# MB_pwr_in.net
KiCad netlist of a schematic drawn in Altium Designer
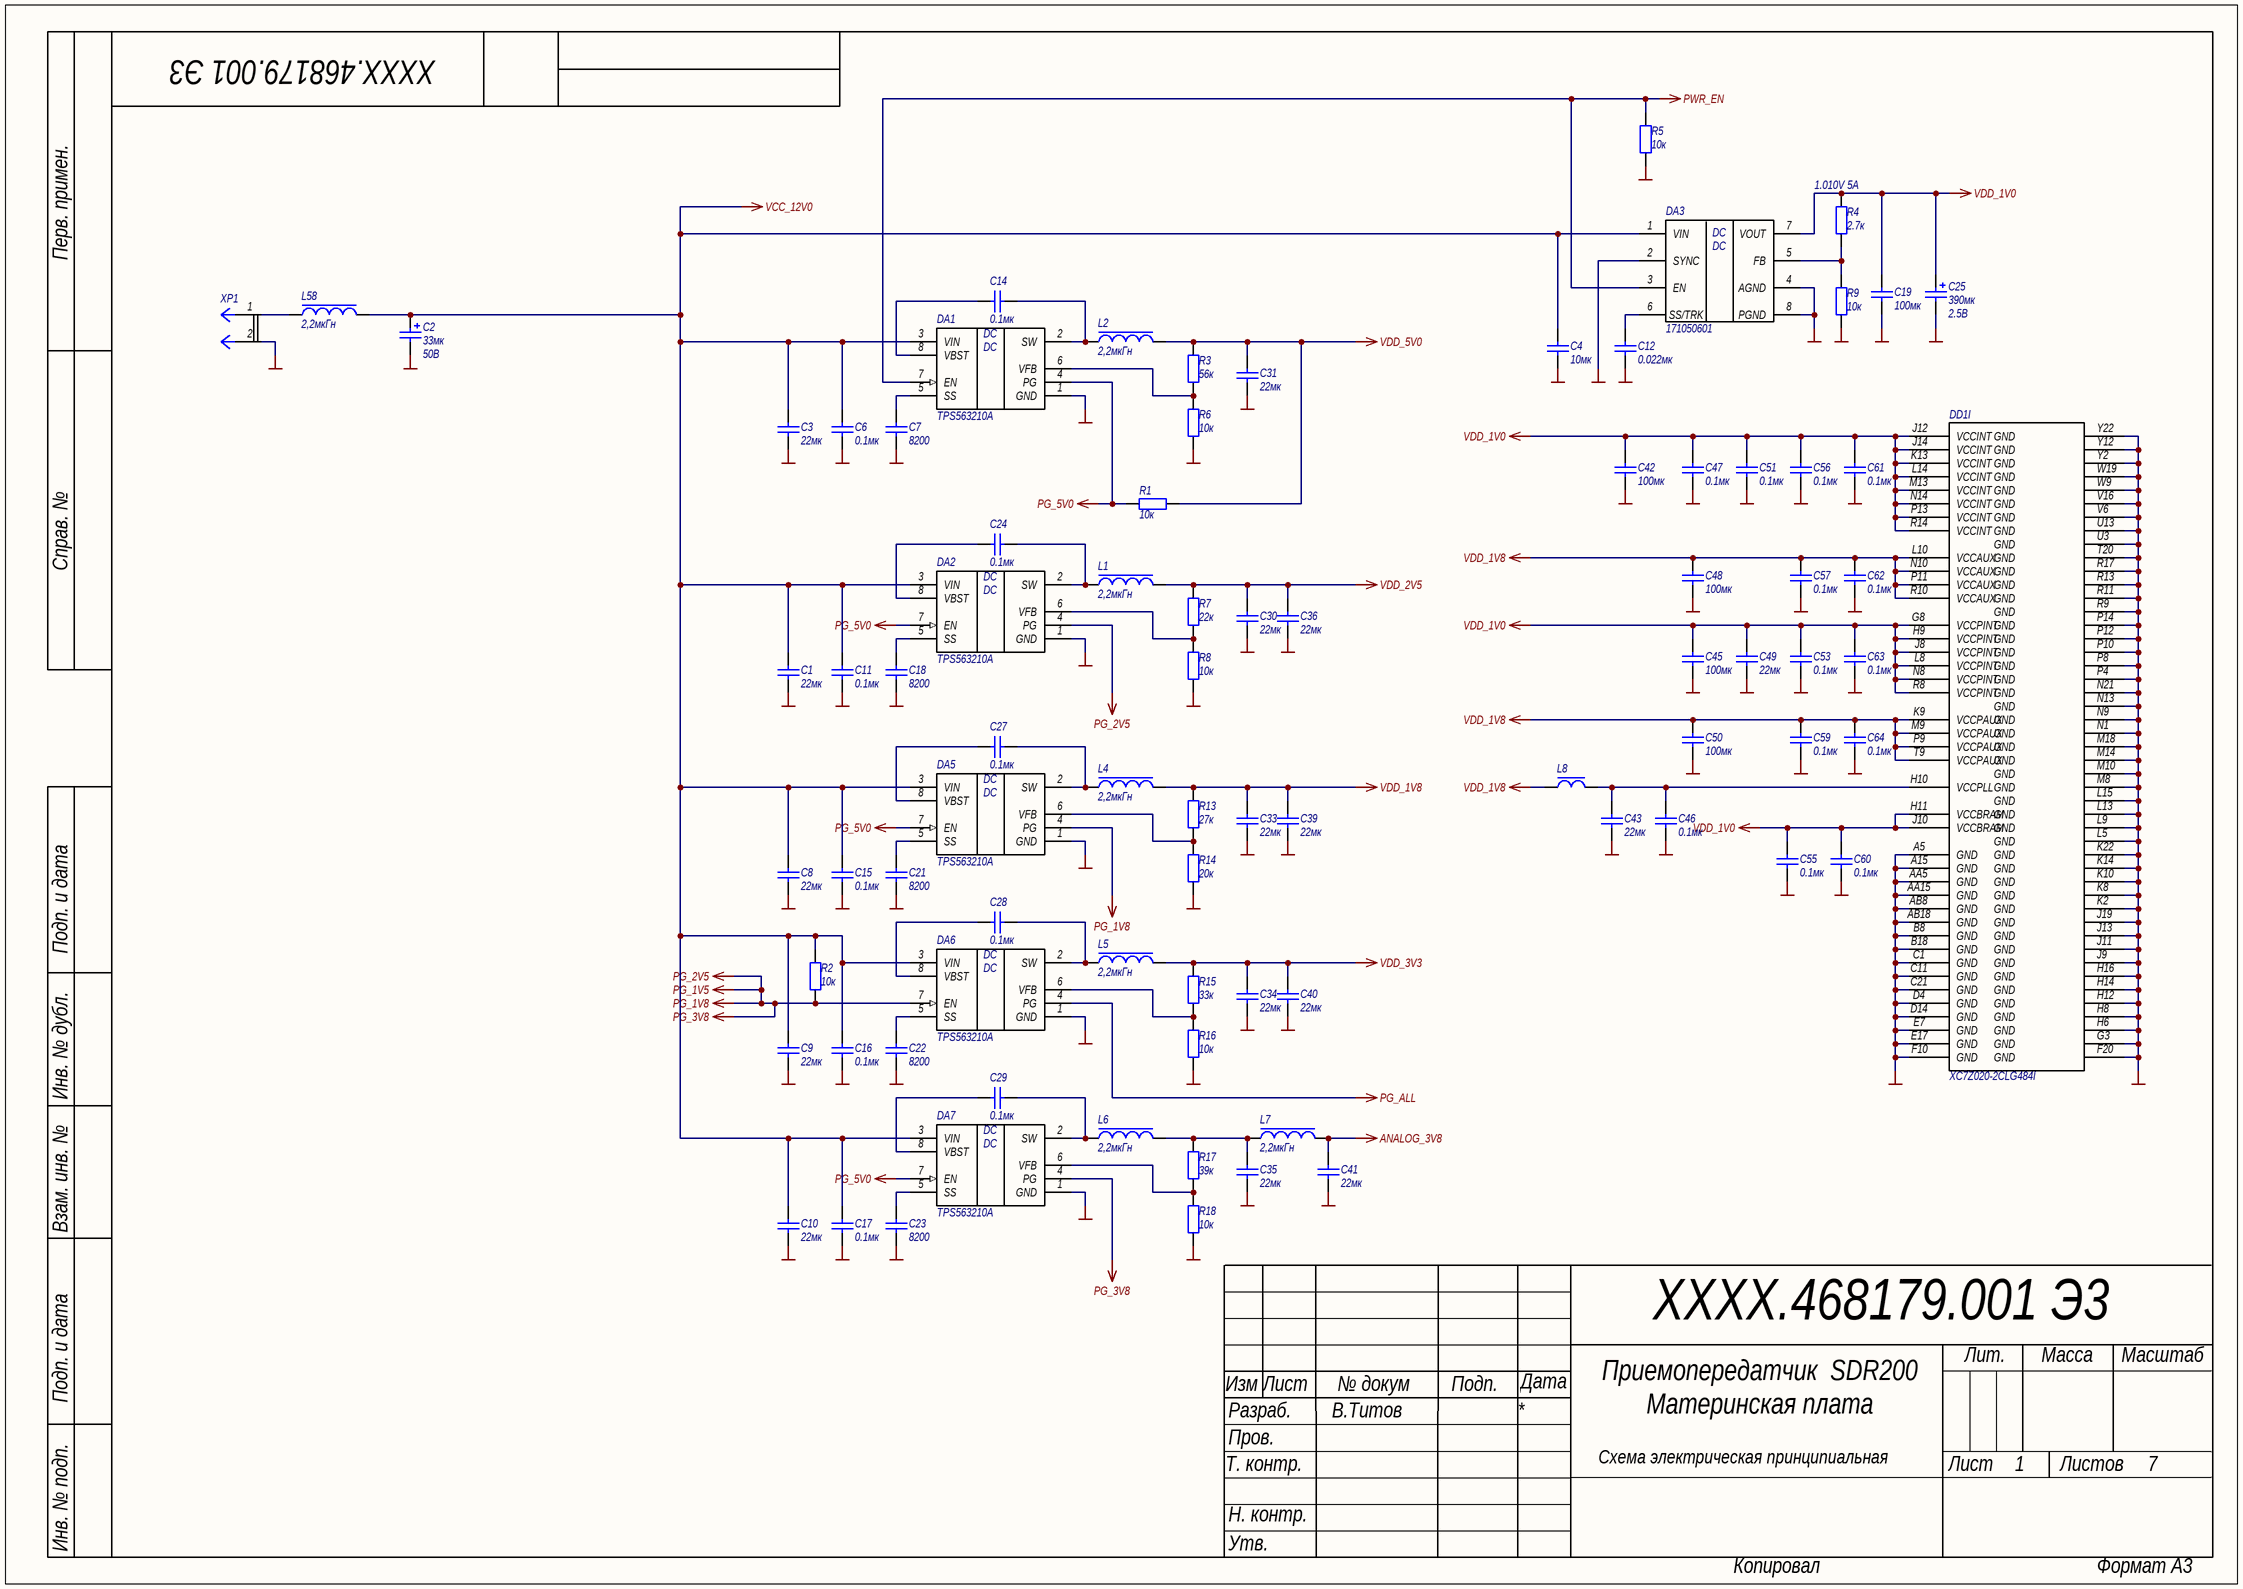
[diagram p0: MB_pwr_in.SchDoc]

(export (version "E")
  (design (tool "Eeschema 10.0.6"))
  (components
    (comp (ref "C1")
      (value "22мк")
      (footprint "CAPC2012X12L")
      (description "Кер. ЧИП-конденсатор")
      (fields (field (name "MANUFACTURER") "TDK") (field (name "TOLERANCE") "±10%"))
      (libsource (lib "nels_caps") (part "Кер.ЧИП конд. 0805 22мкФ X5R 10% 16В"))
    )
    (comp (ref "C2")
      (value "33мк")
      (footprint "CAPAE7664X77L")
      (description "Гибридный ЧИП-конденсатор")
      (fields
        (field (name "TOLERANCE") "±20%")
        (field (name "MANUFACTURERPARTNUMBER") "EEHZC1H330XP")
        (field (name "POWER/VOLTAGE") "50В")
        (field (name "PUBLISHER") "Altium Limited")
      )
      (libsource (lib "p68_l") (part "Конденсатор гибридный SMD 33мкФ ±20% 50В"))
    )
    (comp (ref "C3")
      (value "22мк")
      (footprint "CAPC2012X12L")
      (description "Кер. ЧИП-конденсатор")
      (fields (field (name "MANUFACTURER") "TDK") (field (name "TOLERANCE") "±10%"))
      (libsource (lib "nels_caps") (part "Кер.ЧИП конд. 0805 22мкФ X5R 10% 16В"))
    )
    (comp (ref "C4")
      (value "10мк")
      (footprint "CAPC3225X27L")
      (description "Кер. ЧИП-конденсатор")
      (fields (field (name "MANUFACTURER") "Murata") (field (name "TOLERANCE") "±20%"))
      (libsource (lib "nels") (part "Кер.ЧИП конд. 1210 10мкФ X5R 20% 50В"))
    )
    (comp (ref "C6")
      (value "0.1мк")
      (footprint "CAPC1005X06N")
      (description "Кер. ЧИП-конденсатор")
      (fields (field (name "TOLERANCE") "±10%"))
      (libsource (lib "nels_caps") (part "Кер.ЧИП конд. 0402 0.1мкФ X7R 10%, 16В"))
    )
    (comp (ref "C7")
      (value "8200")
      (footprint "CAPC1005X06N")
      (description "Кер. ЧИП-конденсатор")
      (fields (field (name "TOLERANCE") "±20%"))
      (libsource (lib "nels_caps") (part "Кер.ЧИП конд. 0402 8200пФ X7R 10%, 50В"))
    )
    (comp (ref "C8")
      (value "22мк")
      (footprint "CAPC2012X12L")
      (description "Кер. ЧИП-конденсатор")
      (fields (field (name "MANUFACTURER") "TDK") (field (name "TOLERANCE") "±10%"))
      (libsource (lib "nels_caps") (part "Кер.ЧИП конд. 0805 22мкФ X5R 10% 16В"))
    )
    (comp (ref "C9")
      (value "22мк")
      (footprint "CAPC2012X12L")
      (description "Кер. ЧИП-конденсатор")
      (fields (field (name "MANUFACTURER") "TDK") (field (name "TOLERANCE") "±10%"))
      (libsource (lib "nels_caps") (part "Кер.ЧИП конд. 0805 22мкФ X5R 10% 16В"))
    )
    (comp (ref "C10")
      (value "22мк")
      (footprint "CAPC2012X12L")
      (description "Кер. ЧИП-конденсатор")
      (fields (field (name "MANUFACTURER") "TDK") (field (name "TOLERANCE") "±10%"))
      (libsource (lib "nels_caps") (part "Кер.ЧИП конд. 0805 22мкФ X5R 10% 16В"))
    )
    (comp (ref "C11")
      (value "0.1мк")
      (footprint "CAPC1005X06N")
      (description "Кер. ЧИП-конденсатор")
      (fields (field (name "TOLERANCE") "±10%"))
      (libsource (lib "nels_caps") (part "Кер.ЧИП конд. 0402 0.1мкФ X7R 10%, 16В"))
    )
    (comp (ref "C12")
      (value "0.022мк")
      (footprint "CAPC1005X06N")
      (description "Кер. ЧИП-конденсатор")
      (fields (field (name "TOLERANCE") "±20%"))
      (libsource (lib "nels") (part "Кер.ЧИП конд. 0402 0.022мкФ X7R 10%, 50В"))
    )
    (comp (ref "C14")
      (value "0.1мк")
      (footprint "CAPC1005X06N")
      (description "Кер. ЧИП-конденсатор")
      (fields (field (name "TOLERANCE") "±10%"))
      (libsource (lib "nels") (part "Кер.ЧИП конд. 0402 0.1мкФ X7R 10%, 16В"))
    )
    (comp (ref "C15")
      (value "0.1мк")
      (footprint "CAPC1005X06N")
      (description "Кер. ЧИП-конденсатор")
      (fields (field (name "TOLERANCE") "±10%"))
      (libsource (lib "nels_caps") (part "Кер.ЧИП конд. 0402 0.1мкФ X7R 10%, 16В"))
    )
    (comp (ref "C16")
      (value "0.1мк")
      (footprint "CAPC1005X06N")
      (description "Кер. ЧИП-конденсатор")
      (fields (field (name "TOLERANCE") "±10%"))
      (libsource (lib "nels_caps") (part "Кер.ЧИП конд. 0402 0.1мкФ X7R 10%, 16В"))
    )
    (comp (ref "C17")
      (value "0.1мк")
      (footprint "CAPC1005X06N")
      (description "Кер. ЧИП-конденсатор")
      (fields (field (name "TOLERANCE") "±10%"))
      (libsource (lib "nels_caps") (part "Кер.ЧИП конд. 0402 0.1мкФ X7R 10%, 16В"))
    )
    (comp (ref "C18")
      (value "8200")
      (footprint "CAPC1005X06N")
      (description "Кер. ЧИП-конденсатор")
      (fields (field (name "TOLERANCE") "±20%"))
      (libsource (lib "nels_caps") (part "Кер.ЧИП конд. 0402 8200пФ X7R 10%, 50В"))
    )
    (comp (ref "C19")
      (value "100мк")
      (footprint "CAPC3216X19L")
      (description "Кер. ЧИП-конденсатор")
      (fields (field (name "MANUFACTURER") "Murata") (field (name "TOLERANCE") "±20%"))
      (libsource (lib "nels_caps") (part "Кер.ЧИП конд. 1206 100мкФ X5R 20% 6.3В"))
    )
    (comp (ref "C21")
      (value "8200")
      (footprint "CAPC1005X06N")
      (description "Кер. ЧИП-конденсатор")
      (fields (field (name "TOLERANCE") "±20%"))
      (libsource (lib "nels_caps") (part "Кер.ЧИП конд. 0402 8200пФ X7R 10%, 50В"))
    )
    (comp (ref "C22")
      (value "8200")
      (footprint "CAPC1005X06N")
      (description "Кер. ЧИП-конденсатор")
      (fields (field (name "TOLERANCE") "±20%"))
      (libsource (lib "nels_caps") (part "Кер.ЧИП конд. 0402 8200пФ X7R 10%, 50В"))
    )
    (comp (ref "C23")
      (value "8200")
      (footprint "CAPC1005X06N")
      (description "Кер. ЧИП-конденсатор")
      (fields (field (name "TOLERANCE") "±20%"))
      (libsource (lib "nels_caps") (part "Кер.ЧИП конд. 0402 8200пФ X7R 10%, 50В"))
    )
    (comp (ref "C24")
      (value "0.1мк")
      (footprint "CAPC1005X06N")
      (description "Кер. ЧИП-конденсатор")
      (fields (field (name "TOLERANCE") "±10%"))
      (libsource (lib "nels") (part "Кер.ЧИП конд. 0402 0.1мкФ X7R 10%, 16В"))
    )
    (comp (ref "C25")
      (value "390мк")
      (footprint "CAPAE7266X61N")
      (description "Aluminum Organic Polymer Capacitor")
      (fields
        (field (name "POWER/VOLTAGE") "2.5В")
        (field (name "MANUFACTURER") "Panasonic")
        (field (name "TOLERANCE") "±20%")
        (field (name "PUBLISHER") "Altium Limited")
      )
      (libsource (lib "nels_caps") (part "Конденсатор гибридный SMD 390мкФ ±20% 2.5В"))
    )
    (comp (ref "C27")
      (value "0.1мк")
      (footprint "CAPC1005X06N")
      (description "Кер. ЧИП-конденсатор")
      (fields (field (name "TOLERANCE") "±10%"))
      (libsource (lib "nels") (part "Кер.ЧИП конд. 0402 0.1мкФ X7R 10%, 16В"))
    )
    (comp (ref "C28")
      (value "0.1мк")
      (footprint "CAPC1005X06N")
      (description "Кер. ЧИП-конденсатор")
      (fields (field (name "TOLERANCE") "±10%"))
      (libsource (lib "nels") (part "Кер.ЧИП конд. 0402 0.1мкФ X7R 10%, 16В"))
    )
    (comp (ref "C29")
      (value "0.1мк")
      (footprint "CAPC1005X06N")
      (description "Кер. ЧИП-конденсатор")
      (fields (field (name "TOLERANCE") "±10%"))
      (libsource (lib "nels") (part "Кер.ЧИП конд. 0402 0.1мкФ X7R 10%, 16В"))
    )
    (comp (ref "C30")
      (value "22мк")
      (footprint "CAPC2012X12L")
      (description "Кер. ЧИП-конденсатор")
      (fields (field (name "MANUFACTURER") "TDK") (field (name "TOLERANCE") "±10%"))
      (libsource (lib "nels_caps") (part "Кер.ЧИП конд. 0805 22мкФ X5R 10% 16В"))
    )
    (comp (ref "C31")
      (value "22мк")
      (footprint "CAPC2012X12L")
      (description "Кер. ЧИП-конденсатор")
      (fields (field (name "MANUFACTURER") "TDK") (field (name "TOLERANCE") "±10%"))
      (libsource (lib "nels_caps") (part "Кер.ЧИП конд. 0805 22мкФ X5R 10% 16В"))
    )
    (comp (ref "C33")
      (value "22мк")
      (footprint "CAPC2012X12L")
      (description "Кер. ЧИП-конденсатор")
      (fields (field (name "MANUFACTURER") "TDK") (field (name "TOLERANCE") "±10%"))
      (libsource (lib "nels_caps") (part "Кер.ЧИП конд. 0805 22мкФ X5R 10% 16В"))
    )
    (comp (ref "C34")
      (value "22мк")
      (footprint "CAPC2012X12L")
      (description "Кер. ЧИП-конденсатор")
      (fields (field (name "MANUFACTURER") "TDK") (field (name "TOLERANCE") "±10%"))
      (libsource (lib "nels_caps") (part "Кер.ЧИП конд. 0805 22мкФ X5R 10% 16В"))
    )
    (comp (ref "C35")
      (value "22мк")
      (footprint "CAPC2012X12L")
      (description "Кер. ЧИП-конденсатор")
      (fields (field (name "MANUFACTURER") "TDK") (field (name "TOLERANCE") "±10%"))
      (libsource (lib "nels_caps") (part "Кер.ЧИП конд. 0805 22мкФ X5R 10% 16В"))
    )
    (comp (ref "C36")
      (value "22мк")
      (footprint "CAPC2012X12L")
      (description "Кер. ЧИП-конденсатор")
      (fields (field (name "MANUFACTURER") "TDK") (field (name "TOLERANCE") "±10%"))
      (libsource (lib "nels_caps") (part "Кер.ЧИП конд. 0805 22мкФ X5R 10% 16В"))
    )
    (comp (ref "C39")
      (value "22мк")
      (footprint "CAPC2012X12L")
      (description "Кер. ЧИП-конденсатор")
      (fields (field (name "MANUFACTURER") "TDK") (field (name "TOLERANCE") "±10%"))
      (libsource (lib "nels_caps") (part "Кер.ЧИП конд. 0805 22мкФ X5R 10% 16В"))
    )
    (comp (ref "C40")
      (value "22мк")
      (footprint "CAPC2012X12L")
      (description "Кер. ЧИП-конденсатор")
      (fields (field (name "MANUFACTURER") "TDK") (field (name "TOLERANCE") "±10%"))
      (libsource (lib "nels_caps") (part "Кер.ЧИП конд. 0805 22мкФ X5R 10% 16В"))
    )
    (comp (ref "C41")
      (value "22мк")
      (footprint "CAPC2012X12L")
      (description "Кер. ЧИП-конденсатор")
      (fields (field (name "MANUFACTURER") "TDK") (field (name "TOLERANCE") "±10%"))
      (libsource (lib "nels_caps") (part "Кер.ЧИП конд. 0805 22мкФ X5R 10% 16В"))
    )
    (comp (ref "C42")
      (value "100мк")
      (footprint "CAPC3216X19L")
      (description "Кер. ЧИП-конденсатор")
      (fields (field (name "MANUFACTURER") "Murata") (field (name "TOLERANCE") "±20%"))
      (libsource (lib "nels_caps") (part "Кер.ЧИП конд. 1206 100мкФ X5R 20% 6.3В"))
    )
    (comp (ref "C43")
      (value "22мк")
      (footprint "CAPC2012X12L")
      (description "Кер. ЧИП-конденсатор")
      (fields (field (name "MANUFACTURER") "TDK") (field (name "TOLERANCE") "±10%"))
      (libsource (lib "nels_caps") (part "Кер.ЧИП конд. 0805 22мкФ X5R 10% 16В"))
    )
    (comp (ref "C45")
      (value "100мк")
      (footprint "CAPC3216X19L")
      (description "Кер. ЧИП-конденсатор")
      (fields (field (name "MANUFACTURER") "Murata") (field (name "TOLERANCE") "±20%"))
      (libsource (lib "nels_caps") (part "Кер.ЧИП конд. 1206 100мкФ X5R 20% 6.3В"))
    )
    (comp (ref "C46")
      (value "0.1мк")
      (footprint "CAPC1005X06N")
      (description "Кер. ЧИП-конденсатор")
      (fields (field (name "TOLERANCE") "±10%"))
      (libsource (lib "nels") (part "Кер.ЧИП конд. 0402 0.1мкФ X7R 10%, 16В"))
    )
    (comp (ref "C47")
      (value "0.1мк")
      (footprint "CAPC1005X06N")
      (description "Кер. ЧИП-конденсатор")
      (fields (field (name "TOLERANCE") "±10%"))
      (libsource (lib "nels") (part "Кер.ЧИП конд. 0402 0.1мкФ X7R 10%, 16В"))
    )
    (comp (ref "C48")
      (value "100мк")
      (footprint "CAPC3216X19L")
      (description "Кер. ЧИП-конденсатор")
      (fields (field (name "MANUFACTURER") "Murata") (field (name "TOLERANCE") "±20%"))
      (libsource (lib "nels_caps") (part "Кер.ЧИП конд. 1206 100мкФ X5R 20% 6.3В"))
    )
    (comp (ref "C49")
      (value "22мк")
      (footprint "CAPC2012X12L")
      (description "Кер. ЧИП-конденсатор")
      (fields (field (name "MANUFACTURER") "TDK") (field (name "TOLERANCE") "±10%"))
      (libsource (lib "nels_caps") (part "Кер.ЧИП конд. 0805 22мкФ X5R 10% 16В"))
    )
    (comp (ref "C50")
      (value "100мк")
      (footprint "CAPC3216X19L")
      (description "Кер. ЧИП-конденсатор")
      (fields (field (name "MANUFACTURER") "Murata") (field (name "TOLERANCE") "±20%"))
      (libsource (lib "nels_caps") (part "Кер.ЧИП конд. 1206 100мкФ X5R 20% 6.3В"))
    )
    (comp (ref "C51")
      (value "0.1мк")
      (footprint "CAPC1005X06N")
      (description "Кер. ЧИП-конденсатор")
      (fields (field (name "TOLERANCE") "±10%"))
      (libsource (lib "nels") (part "Кер.ЧИП конд. 0402 0.1мкФ X7R 10%, 16В"))
    )
    (comp (ref "C53")
      (value "0.1мк")
      (footprint "CAPC1005X06N")
      (description "Кер. ЧИП-конденсатор")
      (fields (field (name "TOLERANCE") "±10%"))
      (libsource (lib "nels") (part "Кер.ЧИП конд. 0402 0.1мкФ X7R 10%, 16В"))
    )
    (comp (ref "C55")
      (value "0.1мк")
      (footprint "CAPC1005X06N")
      (description "Кер. ЧИП-конденсатор")
      (fields (field (name "TOLERANCE") "±10%"))
      (libsource (lib "nels") (part "Кер.ЧИП конд. 0402 0.1мкФ X7R 10%, 16В"))
    )
    (comp (ref "C56")
      (value "0.1мк")
      (footprint "CAPC1005X06N")
      (description "Кер. ЧИП-конденсатор")
      (fields (field (name "TOLERANCE") "±10%"))
      (libsource (lib "nels") (part "Кер.ЧИП конд. 0402 0.1мкФ X7R 10%, 16В"))
    )
    (comp (ref "C57")
      (value "0.1мк")
      (footprint "CAPC1005X06N")
      (description "Кер. ЧИП-конденсатор")
      (fields (field (name "TOLERANCE") "±10%"))
      (libsource (lib "nels") (part "Кер.ЧИП конд. 0402 0.1мкФ X7R 10%, 16В"))
    )
    (comp (ref "C59")
      (value "0.1мк")
      (footprint "CAPC1005X06N")
      (description "Кер. ЧИП-конденсатор")
      (fields (field (name "TOLERANCE") "±10%"))
      (libsource (lib "nels") (part "Кер.ЧИП конд. 0402 0.1мкФ X7R 10%, 16В"))
    )
    (comp (ref "C60")
      (value "0.1мк")
      (footprint "CAPC1005X06N")
      (description "Кер. ЧИП-конденсатор")
      (fields (field (name "TOLERANCE") "±10%"))
      (libsource (lib "nels") (part "Кер.ЧИП конд. 0402 0.1мкФ X7R 10%, 16В"))
    )
    (comp (ref "C61")
      (value "0.1мк")
      (footprint "CAPC1005X06N")
      (description "Кер. ЧИП-конденсатор")
      (fields (field (name "TOLERANCE") "±10%"))
      (libsource (lib "nels") (part "Кер.ЧИП конд. 0402 0.1мкФ X7R 10%, 16В"))
    )
    (comp (ref "C62")
      (value "0.1мк")
      (footprint "CAPC1005X06N")
      (description "Кер. ЧИП-конденсатор")
      (fields (field (name "TOLERANCE") "±10%"))
      (libsource (lib "nels") (part "Кер.ЧИП конд. 0402 0.1мкФ X7R 10%, 16В"))
    )
    (comp (ref "C63")
      (value "0.1мк")
      (footprint "CAPC1005X06N")
      (description "Кер. ЧИП-конденсатор")
      (fields (field (name "TOLERANCE") "±10%"))
      (libsource (lib "nels") (part "Кер.ЧИП конд. 0402 0.1мкФ X7R 10%, 16В"))
    )
    (comp (ref "C64")
      (value "0.1мк")
      (footprint "CAPC1005X06N")
      (description "Кер. ЧИП-конденсатор")
      (fields (field (name "TOLERANCE") "±10%"))
      (libsource (lib "nels") (part "Кер.ЧИП конд. 0402 0.1мкФ X7R 10%, 16В"))
    )
    (comp (ref "DA1")
      (value "TPS563210A")
      (footprint "TSOP65P280X110-8N")
      (description "TPS56x210A, 4.5-V to 17-V Input, 2-A, 3-A Synchrono")
      (fields (field (name "MANUFACTURER") "TI"))
      (libsource (lib "MB") (part "Микросхема TPS563210A"))
    )
    (comp (ref "DA2")
      (value "TPS563210A")
      (footprint "MB:TSOP65P280X110-8N")
      (description "TPS56x210A, 4.5-V to 17-V Input, 2-A, 3-A Synchrono")
      (fields (field (name "MANUFACTURER") "TI"))
      (libsource (lib "RF") (part "Микросхема TPS563210A"))
    )
    (comp (ref "DA3")
      (value "171050601")
      (footprint "TO263-7EP")
      (description "MagI3C Power Module VDRM – Variable Step Down Regulator Module")
      (fields (field (name "MANUFACTURER") "Würth Elektronik"))
      (libsource (lib "nels_chip") (part "Микросхема WPMDM1500602JT / 171050601"))
    )
    (comp (ref "DA5")
      (value "TPS563210A")
      (footprint "MB:TSOP65P280X110-8N")
      (description "TPS56x210A, 4.5-V to 17-V Input, 2-A, 3-A Synchrono")
      (fields (field (name "MANUFACTURER") "TI"))
      (libsource (lib "RF") (part "Микросхема TPS563210A"))
    )
    (comp (ref "DA6")
      (value "TPS563210A")
      (footprint "MB:TSOP65P280X110-8N")
      (description "TPS56x210A, 4.5-V to 17-V Input, 2-A, 3-A Synchrono")
      (fields (field (name "MANUFACTURER") "TI"))
      (libsource (lib "RF") (part "Микросхема TPS563210A"))
    )
    (comp (ref "DA7")
      (value "TPS563210A")
      (footprint "MB:TSOP65P280X110-8N")
      (description "TPS56x210A, 4.5-V to 17-V Input, 2-A, 3-A Synchrono")
      (fields (field (name "MANUFACTURER") "TI"))
      (libsource (lib "RF") (part "Микросхема TPS563210A"))
    )
    (comp (ref "DD1")
      (value "XC7Z020-2CLG484I")
      (footprint "BGA484C80P22X22_1900X1900X160")
      (description "Zynq®-7000 SoC Family")
      (fields (field (name "MANUFACTURER") "XILINX"))
      (libsource (lib "MB") (part "Микросхема XC7Z020-2CLG484I"))
    )
    (comp (ref "L1")
      (value "2,2мкГн")
      (footprint "CSAB0420")
      (description "Molding Power Choke")
      (fields
        (field (name "MANUFACTURER") "Vishay")
        (field (name "MANUFACTURERPARTNUMBER") "IHLP1616ABER1R0M11")
      )
      (libsource (lib "nels_ind") (part "ЧИП индуктивность CSAB0420-2R2M"))
    )
    (comp (ref "L2")
      (value "2,2мкГн")
      (footprint "CSAB0420")
      (description "Molding Power Choke")
      (fields
        (field (name "MANUFACTURER") "Vishay")
        (field (name "MANUFACTURERPARTNUMBER") "IHLP1616ABER1R0M11")
      )
      (libsource (lib "nels_ind") (part "ЧИП индуктивность CSAB0420-2R2M"))
    )
    (comp (ref "L4")
      (value "2,2мкГн")
      (footprint "CSAB0420")
      (description "Molding Power Choke")
      (fields
        (field (name "MANUFACTURER") "Vishay")
        (field (name "MANUFACTURERPARTNUMBER") "IHLP1616ABER1R0M11")
      )
      (libsource (lib "nels_ind") (part "ЧИП индуктивность CSAB0420-2R2M"))
    )
    (comp (ref "L5")
      (value "2,2мкГн")
      (footprint "CSAB0420")
      (description "Molding Power Choke")
      (fields
        (field (name "MANUFACTURER") "Vishay")
        (field (name "MANUFACTURERPARTNUMBER") "IHLP1616ABER1R0M11")
      )
      (libsource (lib "nels_ind") (part "ЧИП индуктивность CSAB0420-2R2M"))
    )
    (comp (ref "L6")
      (value "2,2мкГн")
      (footprint "CSAB0420")
      (description "Molding Power Choke")
      (fields
        (field (name "MANUFACTURER") "Vishay")
        (field (name "MANUFACTURERPARTNUMBER") "IHLP1616ABER1R0M11")
      )
      (libsource (lib "nels_ind") (part "ЧИП индуктивность CSAB0420-2R2M"))
    )
    (comp (ref "L7")
      (value "2,2мкГн")
      (footprint "CSAB0420")
      (description "Molding Power Choke")
      (fields
        (field (name "MANUFACTURER") "Vishay")
        (field (name "MANUFACTURERPARTNUMBER") "IHLP1616ABER1R0M11")
      )
      (libsource (lib "nels_ind") (part "ЧИП индуктивность CSAB0420-2R2M"))
    )
    (comp (ref "L8")
      (value "BLM18PG121SN1D")
      (footprint "INDC1608X08L")
      (description "SMD EMI Suppression Filter EMIFIL")
      (fields (field (name "MANUFACTURER") "Murata"))
      (libsource (lib "nels_ind") (part "ЧИП дроссель 0603 BLM18PG121SN1D"))
    )
    (comp (ref "L58")
      (value "2,2мкГн")
      (footprint "CSAB0420")
      (description "Molding Power Choke")
      (fields
        (field (name "MANUFACTURER") "Vishay")
        (field (name "MANUFACTURERPARTNUMBER") "IHLP1616ABER1R0M11")
      )
      (libsource (lib "nels_ind") (part "ЧИП индуктивность CSAB0420-2R2M"))
    )
    (comp (ref "R1")
      (value "10к")
      (footprint "RESC1005X06N")
      (description "ЧИП-резистор")
      (fields (field (name "TOLERANCE") "±5%"))
      (libsource (lib "") (part "Чип резистор 0402 10 кОм, 1%_1"))
    )
    (comp (ref "R2")
      (value "10к")
      (footprint "RESC1005X06N")
      (description "ЧИП-резистор")
      (fields (field (name "TOLERANCE") "±5%"))
      (libsource (lib "nels_res") (part "Чип резистор 0402 10 кОм, 1%"))
    )
    (comp (ref "R3")
      (value "56к")
      (footprint "RESC1005X06N")
      (description "ЧИП-резистор")
      (fields (field (name "TOLERANCE") "±5%"))
      (libsource (lib "nels_res") (part "Чип резистор 0402 56 кОм, 5%"))
    )
    (comp (ref "R4")
      (value "2.7к")
      (footprint "RESC1005X06N")
      (description "ЧИП-резистор")
      (fields (field (name "TOLERANCE") "±5%"))
      (libsource (lib "nels_res") (part "Чип резистор 0402 2,7 кОм, 5%"))
    )
    (comp (ref "R5")
      (value "10к")
      (footprint "RESC1005X06N")
      (description "ЧИП-резистор")
      (fields (field (name "TOLERANCE") "±5%"))
      (libsource (lib "nels_res") (part "Чип резистор 0402 10 кОм, 5%"))
    )
    (comp (ref "R6")
      (value "10к")
      (footprint "RESC1005X06N")
      (description "ЧИП-резистор")
      (fields (field (name "TOLERANCE") "±5%"))
      (libsource (lib "nels_res") (part "Чип резистор 0402 10 кОм, 5%"))
    )
    (comp (ref "R7")
      (value "22к")
      (footprint "RESC1005X06N")
      (description "ЧИП-резистор")
      (fields (field (name "TOLERANCE") "±5%"))
      (libsource (lib "nels_res") (part "Чип резистор 0402 22 кОм, 5%"))
    )
    (comp (ref "R8")
      (value "10к")
      (footprint "RESC1005X06N")
      (description "ЧИП-резистор")
      (fields (field (name "TOLERANCE") "±5%"))
      (libsource (lib "nels_res") (part "Чип резистор 0402 10 кОм, 5%"))
    )
    (comp (ref "R9")
      (value "10к")
      (footprint "RESC1005X06N")
      (description "ЧИП-резистор")
      (fields (field (name "TOLERANCE") "±5%"))
      (libsource (lib "nels_res") (part "Чип резистор 0402 10 кОм, 5%"))
    )
    (comp (ref "R13")
      (value "27к")
      (footprint "RESC1005X06N")
      (description "ЧИП-резистор")
      (fields (field (name "TOLERANCE") "±5%"))
      (libsource (lib "nels_res") (part "Чип резистор 0402 27 кОм, 5%"))
    )
    (comp (ref "R14")
      (value "20к")
      (footprint "RESC1005X06N")
      (description "ЧИП-резистор")
      (fields (field (name "TOLERANCE") "±5%"))
      (libsource (lib "nels_res") (part "Чип резистор 0402 20 кОм, 5%"))
    )
    (comp (ref "R15")
      (value "33к")
      (footprint "RESC1005X06N")
      (description "ЧИП-резистор")
      (fields (field (name "TOLERANCE") "±5%"))
      (libsource (lib "nels_res") (part "Чип резистор 0402 33 кОм, 5%"))
    )
    (comp (ref "R16")
      (value "10к")
      (footprint "RESC1005X06N")
      (description "ЧИП-резистор")
      (fields (field (name "TOLERANCE") "±5%"))
      (libsource (lib "nels_res") (part "Чип резистор 0402 10 кОм, 5%"))
    )
    (comp (ref "R17")
      (value "39к")
      (footprint "RESC1005X06N")
      (description "ЧИП-резистор")
      (fields (field (name "TOLERANCE") "±5%"))
      (libsource (lib "nels_res") (part "Чип резистор 0402 39 кОм, 5%"))
    )
    (comp (ref "R18")
      (value "10к")
      (footprint "RESC1005X06N")
      (description "ЧИП-резистор")
      (fields (field (name "TOLERANCE") "±5%"))
      (libsource (lib "nels_res") (part "Чип резистор 0402 10 кОм, 5%"))
    )
    (comp (ref "XP1")
      (value "XT30UPB-M")
      (footprint "XT30UPB-M")
      (description "AMASS XT30UPB-M  5 mm")
      (libsource (lib "nels_conn") (part "Соединитель XT30UPB-M"))
    )
  )
  (nets
    (net (code "1") (name "ANALOG_3V8") (class "Default")
      (node (ref "C41") (pin "2") (pinfunction "2_2") (pintype "passive"))
      (node (ref "L7") (pin "2") (pinfunction "2_2") (pintype "passive"))
    )
    (net (code "2") (name "GND") (class "Default")
      (node (ref "C1") (pin "1") (pinfunction "1_1") (pintype "passive"))
      (node (ref "C10") (pin "1") (pinfunction "1_1") (pintype "passive"))
      (node (ref "C11") (pin "1") (pinfunction "1_1") (pintype "passive"))
      (node (ref "C12") (pin "1") (pinfunction "1_1") (pintype "passive"))
      (node (ref "C15") (pin "1") (pinfunction "1_1") (pintype "passive"))
      (node (ref "C16") (pin "1") (pinfunction "1_1") (pintype "passive"))
      (node (ref "C17") (pin "1") (pinfunction "1_1") (pintype "passive"))
      (node (ref "C18") (pin "1") (pinfunction "1_1") (pintype "passive"))
      (node (ref "C19") (pin "1") (pinfunction "1_1") (pintype "passive"))
      (node (ref "C2") (pin "2") (pinfunction "2_2") (pintype "passive"))
      (node (ref "C21") (pin "1") (pinfunction "1_1") (pintype "passive"))
      (node (ref "C22") (pin "1") (pinfunction "1_1") (pintype "passive"))
      (node (ref "C23") (pin "1") (pinfunction "1_1") (pintype "passive"))
      (node (ref "C25") (pin "2") (pinfunction "2_2") (pintype "passive"))
      (node (ref "C3") (pin "1") (pinfunction "1_1") (pintype "passive"))
      (node (ref "C30") (pin "1") (pinfunction "1_1") (pintype "passive"))
      (node (ref "C31") (pin "1") (pinfunction "1_1") (pintype "passive"))
      (node (ref "C33") (pin "1") (pinfunction "1_1") (pintype "passive"))
      (node (ref "C34") (pin "1") (pinfunction "1_1") (pintype "passive"))
      (node (ref "C35") (pin "1") (pinfunction "1_1") (pintype "passive"))
      (node (ref "C36") (pin "1") (pinfunction "1_1") (pintype "passive"))
      (node (ref "C39") (pin "1") (pinfunction "1_1") (pintype "passive"))
      (node (ref "C4") (pin "1") (pinfunction "1_1") (pintype "passive"))
      (node (ref "C40") (pin "1") (pinfunction "1_1") (pintype "passive"))
      (node (ref "C41") (pin "1") (pinfunction "1_1") (pintype "passive"))
      (node (ref "C42") (pin "1") (pinfunction "1_1") (pintype "passive"))
      (node (ref "C43") (pin "1") (pinfunction "1_1") (pintype "passive"))
      (node (ref "C45") (pin "1") (pinfunction "1_1") (pintype "passive"))
      (node (ref "C46") (pin "1") (pinfunction "1_1") (pintype "passive"))
      (node (ref "C47") (pin "1") (pinfunction "1_1") (pintype "passive"))
      (node (ref "C48") (pin "1") (pinfunction "1_1") (pintype "passive"))
      (node (ref "C49") (pin "1") (pinfunction "1_1") (pintype "passive"))
      (node (ref "C50") (pin "1") (pinfunction "1_1") (pintype "passive"))
      (node (ref "C51") (pin "1") (pinfunction "1_1") (pintype "passive"))
      (node (ref "C53") (pin "1") (pinfunction "1_1") (pintype "passive"))
      (node (ref "C55") (pin "1") (pinfunction "1_1") (pintype "passive"))
      (node (ref "C56") (pin "1") (pinfunction "1_1") (pintype "passive"))
      (node (ref "C57") (pin "1") (pinfunction "1_1") (pintype "passive"))
      (node (ref "C59") (pin "1") (pinfunction "1_1") (pintype "passive"))
      (node (ref "C6") (pin "1") (pinfunction "1_1") (pintype "passive"))
      (node (ref "C60") (pin "1") (pinfunction "1_1") (pintype "passive"))
      (node (ref "C61") (pin "1") (pinfunction "1_1") (pintype "passive"))
      (node (ref "C62") (pin "1") (pinfunction "1_1") (pintype "passive"))
      (node (ref "C63") (pin "1") (pinfunction "1_1") (pintype "passive"))
      (node (ref "C64") (pin "1") (pinfunction "1_1") (pintype "passive"))
      (node (ref "C7") (pin "1") (pinfunction "1_1") (pintype "passive"))
      (node (ref "C8") (pin "1") (pinfunction "1_1") (pintype "passive"))
      (node (ref "C9") (pin "1") (pinfunction "1_1") (pintype "passive"))
      (node (ref "DA1") (pin "1") (pinfunction "GND_1") (pintype "passive"))
      (node (ref "DA2") (pin "1") (pinfunction "GND_1") (pintype "passive"))
      (node (ref "DA3") (pin "2") (pinfunction "SYNC_2") (pintype "passive"))
      (node (ref "DA3") (pin "4") (pinfunction "AGND_4") (pintype "passive"))
      (node (ref "DA3") (pin "8") (pinfunction "PGND_8") (pintype "passive"))
      (node (ref "DA5") (pin "1") (pinfunction "GND_1") (pintype "passive"))
      (node (ref "DA6") (pin "1") (pinfunction "GND_1") (pintype "passive"))
      (node (ref "DA7") (pin "1") (pinfunction "GND_1") (pintype "passive"))
      (node (ref "DD1") (pin "A15") (pinfunction "GND_A15") (pintype "power_in"))
      (node (ref "DD1") (pin "A5") (pinfunction "GND_A5") (pintype "power_in"))
      (node (ref "DD1") (pin "AA15") (pinfunction "GND_AA15") (pintype "power_in"))
      (node (ref "DD1") (pin "AA5") (pinfunction "GND_AA5") (pintype "power_in"))
      (node (ref "DD1") (pin "AB18") (pinfunction "GND_AB18") (pintype "power_in"))
      (node (ref "DD1") (pin "AB8") (pinfunction "GND_AB8") (pintype "power_in"))
      (node (ref "DD1") (pin "B18") (pinfunction "GND_B18") (pintype "power_in"))
      (node (ref "DD1") (pin "B8") (pinfunction "GND_B8") (pintype "power_in"))
      (node (ref "DD1") (pin "C1") (pinfunction "GND_C1") (pintype "power_in"))
      (node (ref "DD1") (pin "C11") (pinfunction "GND_C11") (pintype "power_in"))
      (node (ref "DD1") (pin "C21") (pinfunction "GND_C21") (pintype "power_in"))
      (node (ref "DD1") (pin "D14") (pinfunction "GND_D14") (pintype "power_in"))
      (node (ref "DD1") (pin "D4") (pinfunction "GND_D4") (pintype "power_in"))
      (node (ref "DD1") (pin "E17") (pinfunction "GND_E17") (pintype "power_in"))
      (node (ref "DD1") (pin "E7") (pinfunction "GND_E7") (pintype "power_in"))
      (node (ref "DD1") (pin "F10") (pinfunction "GND_F10") (pintype "power_in"))
      (node (ref "DD1") (pin "F20") (pinfunction "GND_F20") (pintype "power_in"))
      (node (ref "DD1") (pin "G3") (pinfunction "GND_G3") (pintype "power_in"))
      (node (ref "DD1") (pin "H12") (pinfunction "GND_H12") (pintype "power_in"))
      (node (ref "DD1") (pin "H14") (pinfunction "GND_H14") (pintype "power_in"))
      (node (ref "DD1") (pin "H16") (pinfunction "GND_H16") (pintype "power_in"))
      (node (ref "DD1") (pin "H6") (pinfunction "GND_H6") (pintype "power_in"))
      (node (ref "DD1") (pin "H8") (pinfunction "GND_H8") (pintype "power_in"))
      (node (ref "DD1") (pin "J11") (pinfunction "GND_J11") (pintype "power_in"))
      (node (ref "DD1") (pin "J13") (pinfunction "GND_J13") (pintype "power_in"))
      (node (ref "DD1") (pin "J19") (pinfunction "GND_J19") (pintype "power_in"))
      (node (ref "DD1") (pin "J9") (pinfunction "GND_J9") (pintype "power_in"))
      (node (ref "DD1") (pin "K10") (pinfunction "GND_K10") (pintype "power_in"))
      (node (ref "DD1") (pin "K14") (pinfunction "GND_K14") (pintype "power_in"))
      (node (ref "DD1") (pin "K2") (pinfunction "GND_K2") (pintype "power_in"))
      (node (ref "DD1") (pin "K22") (pinfunction "GND_K22") (pintype "power_in"))
      (node (ref "DD1") (pin "K8") (pinfunction "GND_K8") (pintype "power_in"))
      (node (ref "DD1") (pin "L13") (pinfunction "GND_L13") (pintype "power_in"))
      (node (ref "DD1") (pin "L15") (pinfunction "GND_L15") (pintype "power_in"))
      (node (ref "DD1") (pin "L5") (pinfunction "GND_L5") (pintype "power_in"))
      (node (ref "DD1") (pin "L9") (pinfunction "GND_L9") (pintype "power_in"))
      (node (ref "DD1") (pin "M10") (pinfunction "GND_M10") (pintype "power_in"))
      (node (ref "DD1") (pin "M14") (pinfunction "GND_M14") (pintype "power_in"))
      (node (ref "DD1") (pin "M18") (pinfunction "GND_M18") (pintype "power_in"))
      (node (ref "DD1") (pin "M8") (pinfunction "GND_M8") (pintype "power_in"))
      (node (ref "DD1") (pin "N1") (pinfunction "GND_N1") (pintype "power_in"))
      (node (ref "DD1") (pin "N13") (pinfunction "GND_N13") (pintype "power_in"))
      (node (ref "DD1") (pin "N21") (pinfunction "GND_N21") (pintype "power_in"))
      (node (ref "DD1") (pin "N9") (pinfunction "GND_N9") (pintype "power_in"))
      (node (ref "DD1") (pin "P10") (pinfunction "GND_P10") (pintype "power_in"))
      (node (ref "DD1") (pin "P12") (pinfunction "GND_P12") (pintype "power_in"))
      (node (ref "DD1") (pin "P14") (pinfunction "GND_P14") (pintype "power_in"))
      (node (ref "DD1") (pin "P4") (pinfunction "GND_P4") (pintype "power_in"))
      (node (ref "DD1") (pin "P8") (pinfunction "GND_P8") (pintype "power_in"))
      (node (ref "DD1") (pin "R11") (pinfunction "GND_R11") (pintype "power_in"))
      (node (ref "DD1") (pin "R13") (pinfunction "GND_R13") (pintype "power_in"))
      (node (ref "DD1") (pin "R17") (pinfunction "GND_R17") (pintype "power_in"))
      (node (ref "DD1") (pin "R9") (pinfunction "GND_R9") (pintype "power_in"))
      (node (ref "DD1") (pin "T20") (pinfunction "GND_T20") (pintype "power_in"))
      (node (ref "DD1") (pin "U13") (pinfunction "GND_U13") (pintype "power_in"))
      (node (ref "DD1") (pin "U3") (pinfunction "GND_U3") (pintype "power_in"))
      (node (ref "DD1") (pin "V16") (pinfunction "GND_V16") (pintype "power_in"))
      (node (ref "DD1") (pin "V6") (pinfunction "GND_V6") (pintype "power_in"))
      (node (ref "DD1") (pin "W19") (pinfunction "GND_W19") (pintype "power_in"))
      (node (ref "DD1") (pin "W9") (pinfunction "GND_W9") (pintype "power_in"))
      (node (ref "DD1") (pin "Y12") (pinfunction "GND_Y12") (pintype "power_in"))
      (node (ref "DD1") (pin "Y2") (pinfunction "GND_Y2") (pintype "power_in"))
      (node (ref "DD1") (pin "Y22") (pinfunction "GND_Y22") (pintype "power_in"))
      (node (ref "R14") (pin "2") (pinfunction "2_2") (pintype "passive"))
      (node (ref "R16") (pin "2") (pinfunction "2_2") (pintype "passive"))
      (node (ref "R18") (pin "2") (pinfunction "2_2") (pintype "passive"))
      (node (ref "R5") (pin "2") (pinfunction "2_2") (pintype "passive"))
      (node (ref "R6") (pin "2") (pinfunction "2_2") (pintype "passive"))
      (node (ref "R8") (pin "2") (pinfunction "2_2") (pintype "passive"))
      (node (ref "R9") (pin "2") (pinfunction "2_2") (pintype "passive"))
      (node (ref "XP1") (pin "2") (pinfunction "~_2") (pintype "passive"))
    )
    (net (code "3") (name "Net-(C35-Pad2)") (class "Default")
      (node (ref "C35") (pin "2") (pinfunction "2_2") (pintype "passive"))
      (node (ref "L6") (pin "2") (pinfunction "2_2") (pintype "passive"))
      (node (ref "L7") (pin "1") (pinfunction "1_1") (pintype "passive"))
      (node (ref "R17") (pin "2") (pinfunction "2_2") (pintype "passive"))
    )
    (net (code "4") (name "Net-(DA1-SS)") (class "Default")
      (node (ref "C7") (pin "2") (pinfunction "2_2") (pintype "passive"))
      (node (ref "DA1") (pin "5") (pinfunction "SS_5") (pintype "passive"))
    )
    (net (code "5") (name "Net-(DA1-SW)") (class "Default")
      (node (ref "C14") (pin "1") (pinfunction "1_1") (pintype "passive"))
      (node (ref "DA1") (pin "2") (pinfunction "SW_2") (pintype "passive"))
      (node (ref "L2") (pin "1") (pinfunction "1_1") (pintype "passive"))
    )
    (net (code "6") (name "Net-(DA1-VBST)") (class "Default")
      (node (ref "C14") (pin "2") (pinfunction "2_2") (pintype "passive"))
      (node (ref "DA1") (pin "8") (pinfunction "VBST_8") (pintype "passive"))
    )
    (net (code "7") (name "Net-(DA1-VFB)") (class "Default")
      (node (ref "DA1") (pin "6") (pinfunction "VFB_6") (pintype "passive"))
      (node (ref "R3") (pin "1") (pinfunction "1_1") (pintype "passive"))
      (node (ref "R6") (pin "1") (pinfunction "1_1") (pintype "passive"))
    )
    (net (code "8") (name "Net-(DA2-SS)") (class "Default")
      (node (ref "C18") (pin "2") (pinfunction "2_2") (pintype "passive"))
      (node (ref "DA2") (pin "5") (pinfunction "SS_5") (pintype "passive"))
    )
    (net (code "9") (name "Net-(DA2-SW)") (class "Default")
      (node (ref "C24") (pin "1") (pinfunction "1_1") (pintype "passive"))
      (node (ref "DA2") (pin "2") (pinfunction "SW_2") (pintype "passive"))
      (node (ref "L1") (pin "1") (pinfunction "1_1") (pintype "passive"))
    )
    (net (code "10") (name "Net-(DA2-VBST)") (class "Default")
      (node (ref "C24") (pin "2") (pinfunction "2_2") (pintype "passive"))
      (node (ref "DA2") (pin "8") (pinfunction "VBST_8") (pintype "passive"))
    )
    (net (code "11") (name "Net-(DA2-VFB)") (class "Default")
      (node (ref "DA2") (pin "6") (pinfunction "VFB_6") (pintype "passive"))
      (node (ref "R7") (pin "1") (pinfunction "1_1") (pintype "passive"))
      (node (ref "R8") (pin "1") (pinfunction "1_1") (pintype "passive"))
    )
    (net (code "12") (name "Net-(DA3-FB)") (class "Default")
      (node (ref "DA3") (pin "5") (pinfunction "FB_5") (pintype "passive"))
      (node (ref "R4") (pin "1") (pinfunction "1_1") (pintype "passive"))
      (node (ref "R9") (pin "1") (pinfunction "1_1") (pintype "passive"))
    )
    (net (code "13") (name "Net-(DA3-SS{slash}TRK)") (class "Default")
      (node (ref "C12") (pin "2") (pinfunction "2_2") (pintype "passive"))
      (node (ref "DA3") (pin "6") (pinfunction "SS/TRK_6") (pintype "passive"))
    )
    (net (code "14") (name "Net-(DA5-SS)") (class "Default")
      (node (ref "C21") (pin "2") (pinfunction "2_2") (pintype "passive"))
      (node (ref "DA5") (pin "5") (pinfunction "SS_5") (pintype "passive"))
    )
    (net (code "15") (name "Net-(DA5-SW)") (class "Default")
      (node (ref "C27") (pin "1") (pinfunction "1_1") (pintype "passive"))
      (node (ref "DA5") (pin "2") (pinfunction "SW_2") (pintype "passive"))
      (node (ref "L4") (pin "1") (pinfunction "1_1") (pintype "passive"))
    )
    (net (code "16") (name "Net-(DA5-VBST)") (class "Default")
      (node (ref "C27") (pin "2") (pinfunction "2_2") (pintype "passive"))
      (node (ref "DA5") (pin "8") (pinfunction "VBST_8") (pintype "passive"))
    )
    (net (code "17") (name "Net-(DA5-VFB)") (class "Default")
      (node (ref "DA5") (pin "6") (pinfunction "VFB_6") (pintype "passive"))
      (node (ref "R13") (pin "1") (pinfunction "1_1") (pintype "passive"))
      (node (ref "R14") (pin "1") (pinfunction "1_1") (pintype "passive"))
    )
    (net (code "18") (name "Net-(DA6-SS)") (class "Default")
      (node (ref "C22") (pin "2") (pinfunction "2_2") (pintype "passive"))
      (node (ref "DA6") (pin "5") (pinfunction "SS_5") (pintype "passive"))
    )
    (net (code "19") (name "Net-(DA6-SW)") (class "Default")
      (node (ref "C28") (pin "1") (pinfunction "1_1") (pintype "passive"))
      (node (ref "DA6") (pin "2") (pinfunction "SW_2") (pintype "passive"))
      (node (ref "L5") (pin "1") (pinfunction "1_1") (pintype "passive"))
    )
    (net (code "20") (name "Net-(DA6-VBST)") (class "Default")
      (node (ref "C28") (pin "2") (pinfunction "2_2") (pintype "passive"))
      (node (ref "DA6") (pin "8") (pinfunction "VBST_8") (pintype "passive"))
    )
    (net (code "21") (name "Net-(DA6-VFB)") (class "Default")
      (node (ref "DA6") (pin "6") (pinfunction "VFB_6") (pintype "passive"))
      (node (ref "R15") (pin "1") (pinfunction "1_1") (pintype "passive"))
      (node (ref "R16") (pin "1") (pinfunction "1_1") (pintype "passive"))
    )
    (net (code "22") (name "Net-(DA7-SS)") (class "Default")
      (node (ref "C23") (pin "2") (pinfunction "2_2") (pintype "passive"))
      (node (ref "DA7") (pin "5") (pinfunction "SS_5") (pintype "passive"))
    )
    (net (code "23") (name "Net-(DA7-SW)") (class "Default")
      (node (ref "C29") (pin "1") (pinfunction "1_1") (pintype "passive"))
      (node (ref "DA7") (pin "2") (pinfunction "SW_2") (pintype "passive"))
      (node (ref "L6") (pin "1") (pinfunction "1_1") (pintype "passive"))
    )
    (net (code "24") (name "Net-(DA7-VBST)") (class "Default")
      (node (ref "C29") (pin "2") (pinfunction "2_2") (pintype "passive"))
      (node (ref "DA7") (pin "8") (pinfunction "VBST_8") (pintype "passive"))
    )
    (net (code "25") (name "Net-(DA7-VFB)") (class "Default")
      (node (ref "DA7") (pin "6") (pinfunction "VFB_6") (pintype "passive"))
      (node (ref "R17") (pin "1") (pinfunction "1_1") (pintype "passive"))
      (node (ref "R18") (pin "1") (pinfunction "1_1") (pintype "passive"))
    )
    (net (code "26") (name "Net-(DD1I-VCCPLL)") (class "Default")
      (node (ref "C43") (pin "2") (pinfunction "2_2") (pintype "passive"))
      (node (ref "C46") (pin "2") (pinfunction "2_2") (pintype "passive"))
      (node (ref "DD1") (pin "H10") (pinfunction "VCCPLL_H10") (pintype "power_in"))
      (node (ref "L8") (pin "2") (pinfunction "2_2") (pintype "passive"))
    )
    (net (code "27") (name "Net-(L58-Pad1)") (class "Default")
      (node (ref "L58") (pin "1") (pinfunction "1_1") (pintype "passive"))
      (node (ref "XP1") (pin "1") (pinfunction "~_1") (pintype "passive"))
    )
    (net (code "28") (name "PG_1V5") (class "Default")
      (node (ref "DA2") (pin "4") (pinfunction "PG_4") (pintype "open_collector"))
      (node (ref "DA5") (pin "4") (pinfunction "PG_4") (pintype "open_collector"))
      (node (ref "DA6") (pin "7") (pinfunction "EN_7") (pintype "input"))
      (node (ref "DA7") (pin "4") (pinfunction "PG_4") (pintype "open_collector"))
      (node (ref "R2") (pin "1") (pinfunction "1_1") (pintype "passive"))
    )
    (net (code "29") (name "PG_5V0") (class "Default")
      (node (ref "DA1") (pin "4") (pinfunction "PG_4") (pintype "open_collector"))
      (node (ref "DA2") (pin "7") (pinfunction "EN_7") (pintype "input"))
      (node (ref "DA5") (pin "7") (pinfunction "EN_7") (pintype "input"))
      (node (ref "DA7") (pin "7") (pinfunction "EN_7") (pintype "input"))
      (node (ref "R1") (pin "2") (pinfunction "2_2") (pintype "passive"))
    )
    (net (code "30") (name "PG_ALL") (class "Default")
      (node (ref "DA6") (pin "4") (pinfunction "PG_4") (pintype "open_collector"))
    )
    (net (code "31") (name "PWR_EN") (class "Default")
      (node (ref "DA1") (pin "7") (pinfunction "EN_7") (pintype "input"))
      (node (ref "DA3") (pin "3") (pinfunction "EN_3") (pintype "passive"))
      (node (ref "R5") (pin "1") (pinfunction "1_1") (pintype "passive"))
    )
    (net (code "32") (name "VCC_12V0") (class "Default")
      (node (ref "C1") (pin "2") (pinfunction "2_2") (pintype "passive"))
      (node (ref "C10") (pin "2") (pinfunction "2_2") (pintype "passive"))
      (node (ref "C11") (pin "2") (pinfunction "2_2") (pintype "passive"))
      (node (ref "C15") (pin "2") (pinfunction "2_2") (pintype "passive"))
      (node (ref "C16") (pin "2") (pinfunction "2_2") (pintype "passive"))
      (node (ref "C17") (pin "2") (pinfunction "2_2") (pintype "passive"))
      (node (ref "C2") (pin "1") (pinfunction "1_1") (pintype "passive"))
      (node (ref "C3") (pin "2") (pinfunction "2_2") (pintype "passive"))
      (node (ref "C4") (pin "2") (pinfunction "2_2") (pintype "passive"))
      (node (ref "C6") (pin "2") (pinfunction "2_2") (pintype "passive"))
      (node (ref "C8") (pin "2") (pinfunction "2_2") (pintype "passive"))
      (node (ref "C9") (pin "2") (pinfunction "2_2") (pintype "passive"))
      (node (ref "DA1") (pin "3") (pinfunction "VIN_3") (pintype "passive"))
      (node (ref "DA2") (pin "3") (pinfunction "VIN_3") (pintype "passive"))
      (node (ref "DA3") (pin "1") (pinfunction "VIN_1") (pintype "passive"))
      (node (ref "DA5") (pin "3") (pinfunction "VIN_3") (pintype "passive"))
      (node (ref "DA6") (pin "3") (pinfunction "VIN_3") (pintype "passive"))
      (node (ref "DA7") (pin "3") (pinfunction "VIN_3") (pintype "passive"))
      (node (ref "L58") (pin "2") (pinfunction "2_2") (pintype "passive"))
      (node (ref "R2") (pin "2") (pinfunction "2_2") (pintype "passive"))
    )
    (net (code "33") (name "VDD_1V0") (class "Default")
      (node (ref "C19") (pin "2") (pinfunction "2_2") (pintype "passive"))
      (node (ref "C25") (pin "1") (pinfunction "1_1") (pintype "passive"))
      (node (ref "C42") (pin "2") (pinfunction "2_2") (pintype "passive"))
      (node (ref "C45") (pin "2") (pinfunction "2_2") (pintype "passive"))
      (node (ref "C47") (pin "2") (pinfunction "2_2") (pintype "passive"))
      (node (ref "C49") (pin "2") (pinfunction "2_2") (pintype "passive"))
      (node (ref "C51") (pin "2") (pinfunction "2_2") (pintype "passive"))
      (node (ref "C53") (pin "2") (pinfunction "2_2") (pintype "passive"))
      (node (ref "C55") (pin "2") (pinfunction "2_2") (pintype "passive"))
      (node (ref "C56") (pin "2") (pinfunction "2_2") (pintype "passive"))
      (node (ref "C60") (pin "2") (pinfunction "2_2") (pintype "passive"))
      (node (ref "C61") (pin "2") (pinfunction "2_2") (pintype "passive"))
      (node (ref "C63") (pin "2") (pinfunction "2_2") (pintype "passive"))
      (node (ref "DA3") (pin "7") (pinfunction "VOUT_7") (pintype "passive"))
      (node (ref "DD1") (pin "G8") (pinfunction "VCCPINT_G8") (pintype "power_in"))
      (node (ref "DD1") (pin "H11") (pinfunction "VCCBRAM_H11") (pintype "power_in"))
      (node (ref "DD1") (pin "H9") (pinfunction "VCCPINT_H9") (pintype "power_in"))
      (node (ref "DD1") (pin "J10") (pinfunction "VCCBRAM_J10") (pintype "power_in"))
      (node (ref "DD1") (pin "J12") (pinfunction "VCCINT_J12") (pintype "power_in"))
      (node (ref "DD1") (pin "J14") (pinfunction "VCCINT_J14") (pintype "power_in"))
      (node (ref "DD1") (pin "J8") (pinfunction "VCCPINT_J8") (pintype "power_in"))
      (node (ref "DD1") (pin "K13") (pinfunction "VCCINT_K13") (pintype "power_in"))
      (node (ref "DD1") (pin "L14") (pinfunction "VCCINT_L14") (pintype "power_in"))
      (node (ref "DD1") (pin "L8") (pinfunction "VCCPINT_L8") (pintype "power_in"))
      (node (ref "DD1") (pin "M13") (pinfunction "VCCINT_M13") (pintype "power_in"))
      (node (ref "DD1") (pin "N14") (pinfunction "VCCINT_N14") (pintype "power_in"))
      (node (ref "DD1") (pin "N8") (pinfunction "VCCPINT_N8") (pintype "power_in"))
      (node (ref "DD1") (pin "P13") (pinfunction "VCCINT_P13") (pintype "power_in"))
      (node (ref "DD1") (pin "R14") (pinfunction "VCCINT_R14") (pintype "power_in"))
      (node (ref "DD1") (pin "R8") (pinfunction "VCCPINT_R8") (pintype "power_in"))
      (node (ref "R4") (pin "2") (pinfunction "2_2") (pintype "passive"))
    )
    (net (code "34") (name "VDD_1V8") (class "Default")
      (node (ref "C33") (pin "2") (pinfunction "2_2") (pintype "passive"))
      (node (ref "C39") (pin "2") (pinfunction "2_2") (pintype "passive"))
      (node (ref "C48") (pin "2") (pinfunction "2_2") (pintype "passive"))
      (node (ref "C50") (pin "2") (pinfunction "2_2") (pintype "passive"))
      (node (ref "C57") (pin "2") (pinfunction "2_2") (pintype "passive"))
      (node (ref "C59") (pin "2") (pinfunction "2_2") (pintype "passive"))
      (node (ref "C62") (pin "2") (pinfunction "2_2") (pintype "passive"))
      (node (ref "C64") (pin "2") (pinfunction "2_2") (pintype "passive"))
      (node (ref "DD1") (pin "K9") (pinfunction "VCCPAUX_K9") (pintype "power_in"))
      (node (ref "DD1") (pin "L10") (pinfunction "VCCAUX_L10") (pintype "power_in"))
      (node (ref "DD1") (pin "M9") (pinfunction "VCCPAUX_M9") (pintype "power_in"))
      (node (ref "DD1") (pin "N10") (pinfunction "VCCAUX_N10") (pintype "power_in"))
      (node (ref "DD1") (pin "P11") (pinfunction "VCCAUX_P11") (pintype "power_in"))
      (node (ref "DD1") (pin "P9") (pinfunction "VCCPAUX_P9") (pintype "power_in"))
      (node (ref "DD1") (pin "R10") (pinfunction "VCCAUX_R10") (pintype "power_in"))
      (node (ref "DD1") (pin "T9") (pinfunction "VCCPAUX_T9") (pintype "power_in"))
      (node (ref "L4") (pin "2") (pinfunction "2_2") (pintype "passive"))
      (node (ref "L8") (pin "1") (pinfunction "1_1") (pintype "passive"))
      (node (ref "R13") (pin "2") (pinfunction "2_2") (pintype "passive"))
    )
    (net (code "35") (name "VDD_2V5") (class "Default")
      (node (ref "C30") (pin "2") (pinfunction "2_2") (pintype "passive"))
      (node (ref "C36") (pin "2") (pinfunction "2_2") (pintype "passive"))
      (node (ref "L1") (pin "2") (pinfunction "2_2") (pintype "passive"))
      (node (ref "R7") (pin "2") (pinfunction "2_2") (pintype "passive"))
    )
    (net (code "36") (name "VDD_3V3") (class "Default")
      (node (ref "C34") (pin "2") (pinfunction "2_2") (pintype "passive"))
      (node (ref "C40") (pin "2") (pinfunction "2_2") (pintype "passive"))
      (node (ref "L5") (pin "2") (pinfunction "2_2") (pintype "passive"))
      (node (ref "R15") (pin "2") (pinfunction "2_2") (pintype "passive"))
    )
    (net (code "37") (name "VDD_5V0") (class "Default")
      (node (ref "C31") (pin "2") (pinfunction "2_2") (pintype "passive"))
      (node (ref "L2") (pin "2") (pinfunction "2_2") (pintype "passive"))
      (node (ref "R1") (pin "1") (pinfunction "1_1") (pintype "passive"))
      (node (ref "R3") (pin "2") (pinfunction "2_2") (pintype "passive"))
    )
  )
)
